# HDC100X-Breakout_v10.net
KiCad netlist of a schematic drawn in EAGLE
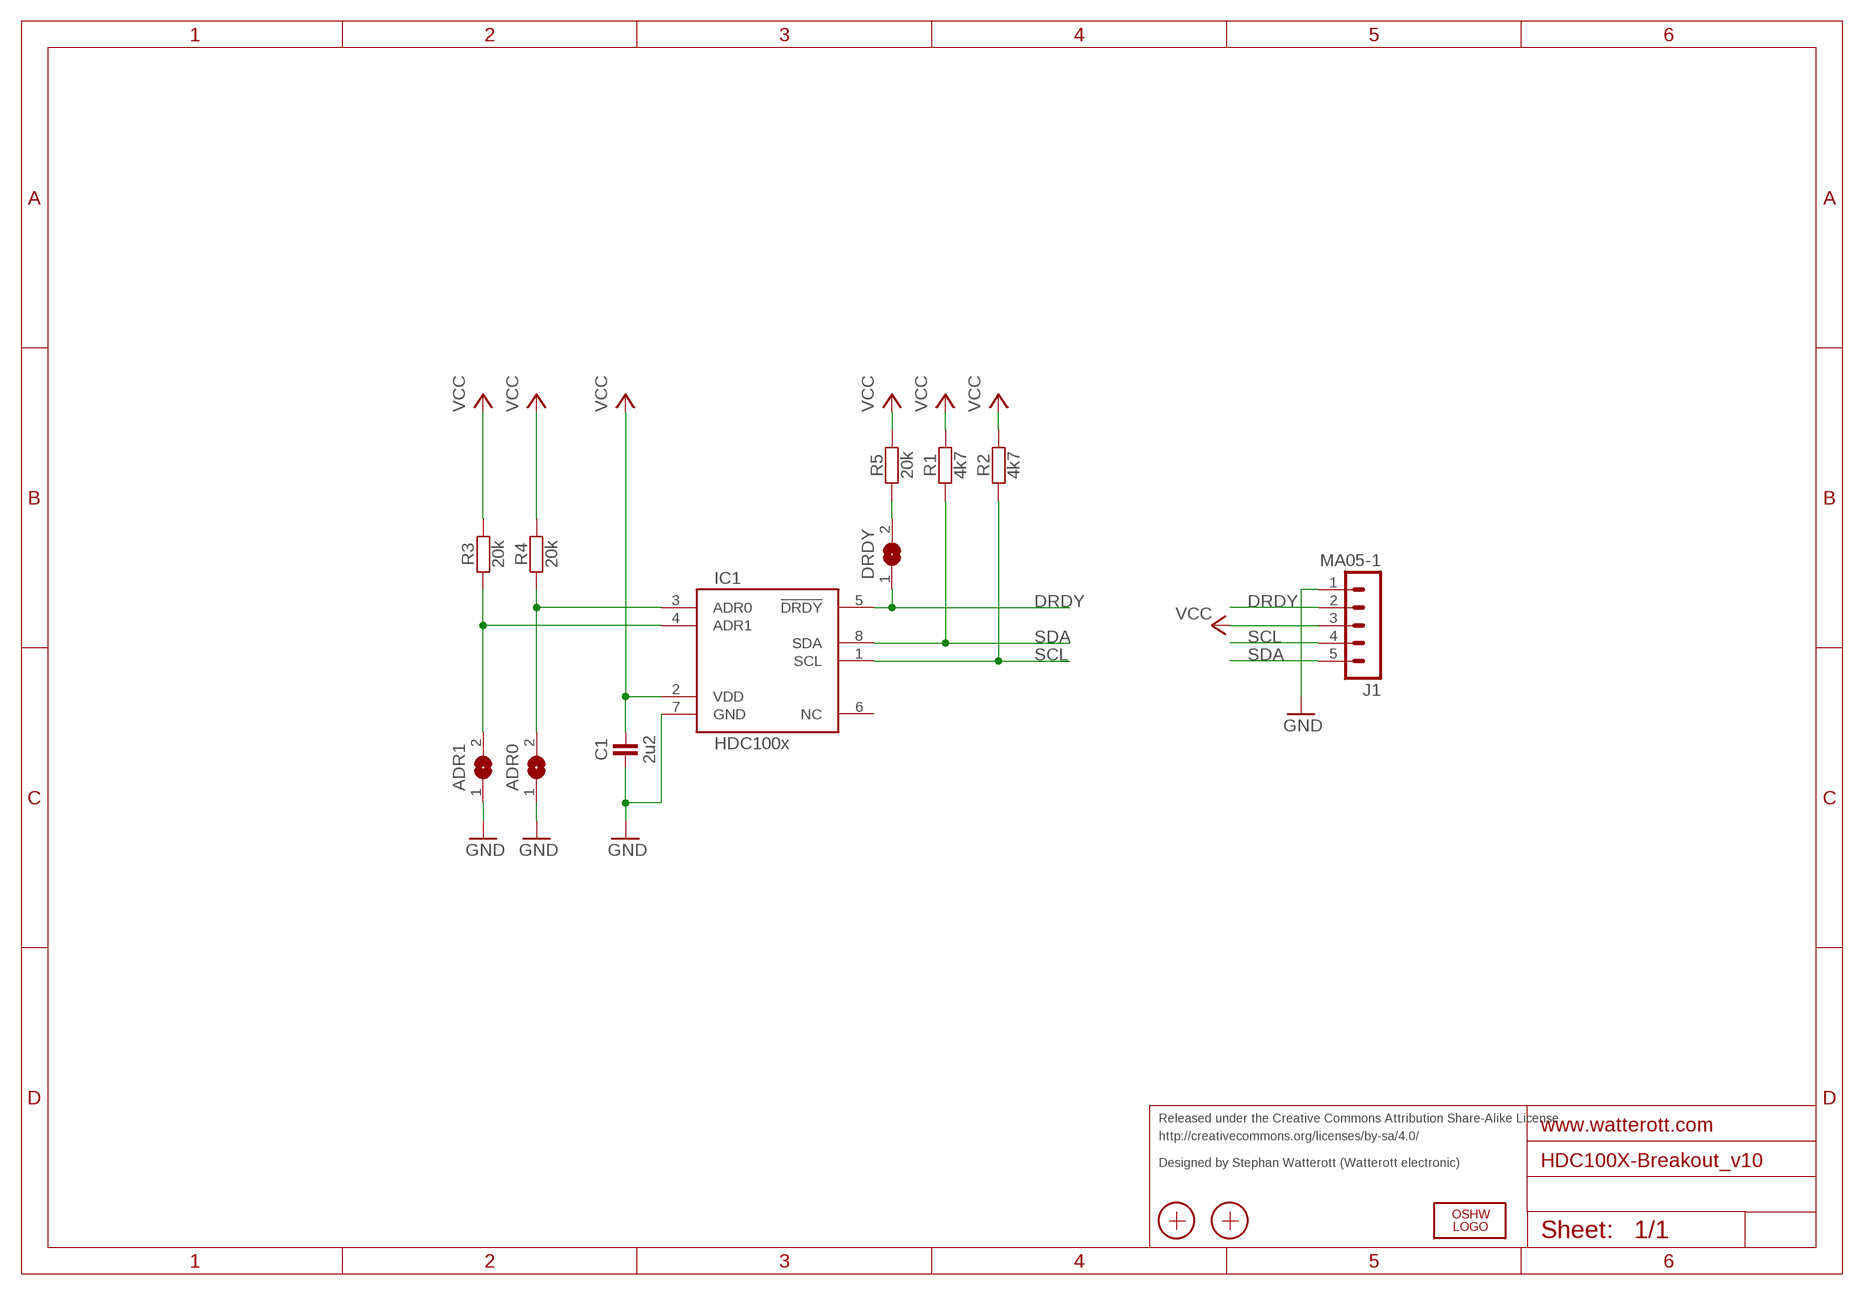
[diagram p0: schematic, sheet 1]

(export (version "E")
  (design (tool "Eeschema 10.0.6"))
  (components
    (comp (ref "ADR0")
      (value "JUMPER2-0402")
      (footprint "eagle-import:JUMPER2-0402")
      (libsource (lib "eagle-import") (part "JUMPER2-0402"))
    )
    (comp (ref "ADR1")
      (value "JUMPER2-0402")
      (footprint "eagle-import:JUMPER2-0402")
      (libsource (lib "eagle-import") (part "JUMPER2-0402"))
    )
    (comp (ref "C1")
      (value "2u2")
      (footprint "eagle-import:R0402")
      (libsource (lib "eagle-import") (part "CAPACITOR-C0402"))
    )
    (comp (ref "DRDY")
      (value "JUMPER2-0402")
      (footprint "eagle-import:JUMPER2-0402")
      (libsource (lib "eagle-import") (part "JUMPER2-0402"))
    )
    (comp (ref "IC1")
      (value "HDC100x")
      (footprint "eagle-import:WLCSP")
      (libsource (lib "eagle-import") (part "HDC1008"))
    )
    (comp (ref "J1")
      (value "MA05-1")
      (footprint "eagle-import:MA05-1")
      (libsource (lib "eagle-import") (part "MA05-1"))
    )
    (comp (ref "LOGO2")
      (value "OSHW_LOGOX0070")
      (footprint "eagle-import:OSHW_6X70")
      (libsource (lib "eagle-import") (part "OSHW_LOGOX0070"))
    )
    (comp (ref "R1")
      (value "4k7")
      (footprint "eagle-import:R0402")
      (libsource (lib "eagle-import") (part "RESISTOR-R0402"))
    )
    (comp (ref "R2")
      (value "4k7")
      (footprint "eagle-import:R0402")
      (libsource (lib "eagle-import") (part "RESISTOR-R0402"))
    )
    (comp (ref "R3")
      (value "20k")
      (footprint "eagle-import:R0402")
      (libsource (lib "eagle-import") (part "RESISTOR-R0402"))
    )
    (comp (ref "R4")
      (value "20k")
      (footprint "eagle-import:R0402")
      (libsource (lib "eagle-import") (part "RESISTOR-R0402"))
    )
    (comp (ref "R5")
      (value "20k")
      (footprint "eagle-import:R0402")
      (libsource (lib "eagle-import") (part "RESISTOR-R0402"))
    )
    (comp (ref "X1")
      (value "PASSER-07")
      (footprint "eagle-import:PASSER_07MM")
      (libsource (lib "eagle-import") (part "PASSER-07"))
    )
    (comp (ref "X2")
      (value "PASSER-07")
      (footprint "eagle-import:PASSER_07MM")
      (libsource (lib "eagle-import") (part "PASSER-07"))
    )
  )
  (nets
    (net (code "1") (name "/DRDY") (class "Default")
      (node (ref "DRDY") (pin "1") (pinfunction "1_1") (pintype "passive"))
      (node (ref "IC1") (pin "5") (pinfunction "~{DRDY}_5") (pintype "output"))
      (node (ref "J1") (pin "2") (pinfunction "2_2") (pintype "passive"))
    )
    (net (code "2") (name "/SCL") (class "Default")
      (node (ref "IC1") (pin "1") (pinfunction "SCL_1") (pintype "input"))
      (node (ref "J1") (pin "4") (pinfunction "4_4") (pintype "passive"))
      (node (ref "R2") (pin "1") (pinfunction "1_1") (pintype "passive"))
    )
    (net (code "3") (name "/SDA") (class "Default")
      (node (ref "IC1") (pin "8") (pinfunction "SDA_8") (pintype "bidirectional"))
      (node (ref "J1") (pin "5") (pinfunction "5_5") (pintype "passive"))
      (node (ref "R1") (pin "1") (pinfunction "1_1") (pintype "passive"))
    )
    (net (code "4") (name "GND") (class "Default")
      (node (ref "ADR0") (pin "1") (pinfunction "1_1") (pintype "passive"))
      (node (ref "ADR1") (pin "1") (pinfunction "1_1") (pintype "passive"))
      (node (ref "C1") (pin "1") (pinfunction "1_1") (pintype "passive"))
      (node (ref "IC1") (pin "7") (pinfunction "GND_7") (pintype "power_in"))
      (node (ref "J1") (pin "1") (pinfunction "1_1") (pintype "passive"))
    )
    (net (code "5") (name "Net-(DRDY-Pad2)") (class "Default")
      (node (ref "DRDY") (pin "2") (pinfunction "2_2") (pintype "passive"))
      (node (ref "R5") (pin "1") (pinfunction "1_1") (pintype "passive"))
    )
    (net (code "6") (name "Net-(IC1-ADR0)") (class "Default")
      (node (ref "ADR0") (pin "2") (pinfunction "2_2") (pintype "passive"))
      (node (ref "IC1") (pin "3") (pinfunction "ADR0_3") (pintype "input"))
      (node (ref "R4") (pin "1") (pinfunction "1_1") (pintype "passive"))
    )
    (net (code "7") (name "Net-(IC1-ADR1)") (class "Default")
      (node (ref "ADR1") (pin "2") (pinfunction "2_2") (pintype "passive"))
      (node (ref "IC1") (pin "4") (pinfunction "ADR1_4") (pintype "input"))
      (node (ref "R3") (pin "1") (pinfunction "1_1") (pintype "passive"))
    )
    (net (code "8") (name "VCC") (class "Default")
      (node (ref "C1") (pin "2") (pinfunction "2_2") (pintype "passive"))
      (node (ref "IC1") (pin "2") (pinfunction "VDD_2") (pintype "power_in"))
      (node (ref "J1") (pin "3") (pinfunction "3_3") (pintype "passive"))
      (node (ref "R1") (pin "2") (pinfunction "2_2") (pintype "passive"))
      (node (ref "R2") (pin "2") (pinfunction "2_2") (pintype "passive"))
      (node (ref "R3") (pin "2") (pinfunction "2_2") (pintype "passive"))
      (node (ref "R4") (pin "2") (pinfunction "2_2") (pintype "passive"))
      (node (ref "R5") (pin "2") (pinfunction "2_2") (pintype "passive"))
    )
    (net (code "9") (name "unconnected-(IC1-NC-Pad6)") (class "Default")
      (node (ref "IC1") (pin "6") (pinfunction "NC_6") (pintype "no_connect"))
    )
  )
)
